# foc_board.net
KiCad netlist of a schematic drawn in EasyEDA Pro
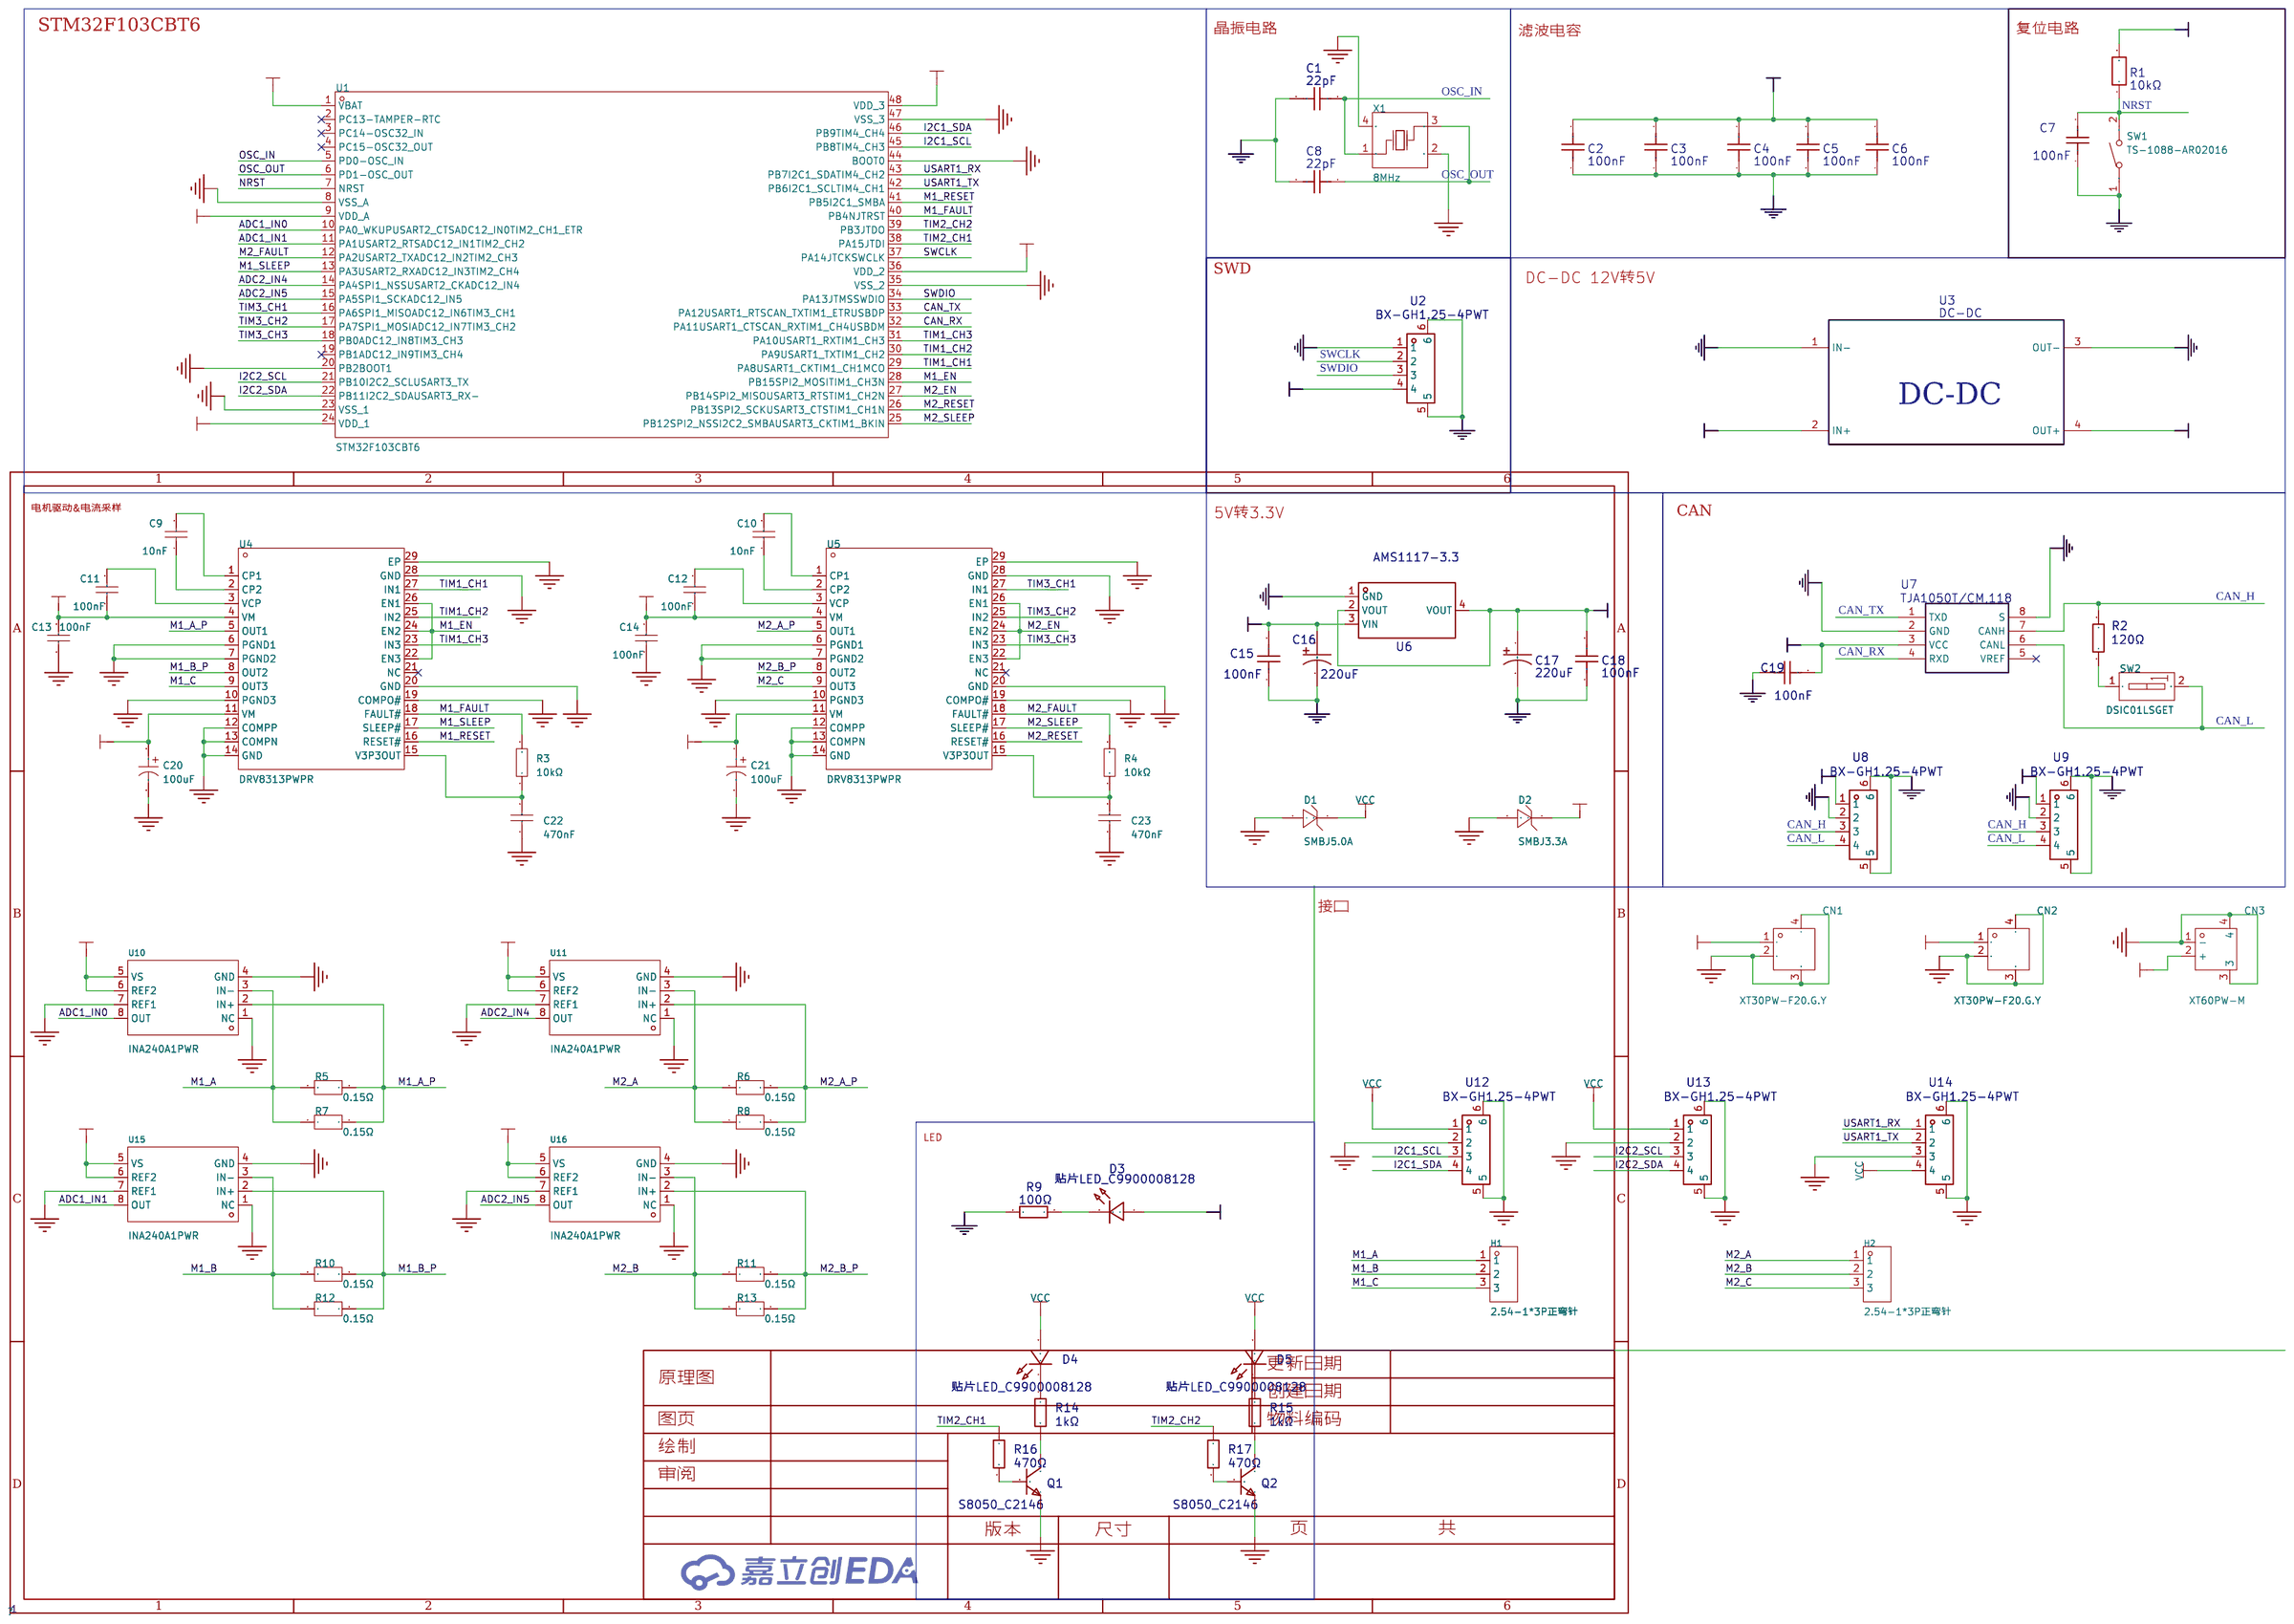
[diagram p0: schematic sheet]

(export (version "E")
  (design (tool "Eeschema 10.0.6"))
  (components
    (comp (ref "C1")
      (value "22pF")
      (footprint "easyedapro:C0603")
      (fields
        (field (name "Manufacturer Part") "0603J0250104KXR")
        (field (name "Manufacturer") "Knowles(楼氏)")
      )
      (libsource (lib "easyedapro") (part "22pF"))
    )
    (comp (ref "C2")
      (value "100nF")
      (footprint "easyedapro:C0603")
      (fields
        (field (name "Manufacturer Part") "0603J0250104KXR")
        (field (name "Manufacturer") "Knowles(楼氏)")
      )
      (libsource (lib "easyedapro") (part "100nF"))
    )
    (comp (ref "C3")
      (value "100nF")
      (footprint "easyedapro:C0603")
      (fields
        (field (name "Manufacturer Part") "0603J0250104KXR")
        (field (name "Manufacturer") "Knowles(楼氏)")
      )
      (libsource (lib "easyedapro") (part "100nF"))
    )
    (comp (ref "C4")
      (value "100nF")
      (footprint "easyedapro:C0603")
      (fields
        (field (name "Manufacturer Part") "0603J0250104KXR")
        (field (name "Manufacturer") "Knowles(楼氏)")
      )
      (libsource (lib "easyedapro") (part "100nF"))
    )
    (comp (ref "C5")
      (value "100nF")
      (footprint "easyedapro:C0603")
      (fields
        (field (name "Manufacturer Part") "0603J0250104KXR")
        (field (name "Manufacturer") "Knowles(楼氏)")
      )
      (libsource (lib "easyedapro") (part "100nF"))
    )
    (comp (ref "C6")
      (value "100nF")
      (footprint "easyedapro:C0603")
      (fields
        (field (name "Manufacturer Part") "0603J0250104KXR")
        (field (name "Manufacturer") "Knowles(楼氏)")
      )
      (libsource (lib "easyedapro") (part "100nF"))
    )
    (comp (ref "C7")
      (value "100nF")
      (footprint "easyedapro:C0603")
      (fields
        (field (name "Manufacturer Part") "0603J0250104KXR")
        (field (name "Manufacturer") "Knowles(楼氏)")
      )
      (libsource (lib "easyedapro") (part "100nF"))
    )
    (comp (ref "C8")
      (value "22pF")
      (footprint "easyedapro:C0603")
      (fields
        (field (name "Manufacturer Part") "0603J0250104KXR")
        (field (name "Manufacturer") "Knowles(楼氏)")
      )
      (libsource (lib "easyedapro") (part "22pF"))
    )
    (comp (ref "C9")
      (value "10nF")
      (footprint "easyedapro:C0603")
      (description "容值:10nF;精度:±10%;额定电压:50V;材质(温度系数):X7R;")
      (fields
        (field (name "Manufacturer Part") "CC0603KRX7R9BB103")
        (field (name "Manufacturer") "YAGEO(国巨)")
      )
      (libsource (lib "easyedapro") (part "CC0603KRX7R9BB103"))
    )
    (comp (ref "C10")
      (value "10nF")
      (footprint "easyedapro:C0603")
      (description "容值:10nF;精度:±10%;额定电压:50V;材质(温度系数):X7R;")
      (fields
        (field (name "Manufacturer Part") "CC0603KRX7R9BB103")
        (field (name "Manufacturer") "YAGEO(国巨)")
      )
      (libsource (lib "easyedapro") (part "CC0603KRX7R9BB103"))
    )
    (comp (ref "C11")
      (value "100nF")
      (footprint "easyedapro:C0603")
      (description "容值:10nF;精度:±10%;额定电压:50V;材质(温度系数):X7R;")
      (fields
        (field (name "Manufacturer Part") "CC0603KRX7R9BB103")
        (field (name "Manufacturer") "YAGEO(国巨)")
      )
      (libsource (lib "easyedapro") (part "CC0603KRX7R9BB103"))
    )
    (comp (ref "C12")
      (value "100nF")
      (footprint "easyedapro:C0603")
      (description "容值:10nF;精度:±10%;额定电压:50V;材质(温度系数):X7R;")
      (fields
        (field (name "Manufacturer Part") "CC0603KRX7R9BB103")
        (field (name "Manufacturer") "YAGEO(国巨)")
      )
      (libsource (lib "easyedapro") (part "CC0603KRX7R9BB103"))
    )
    (comp (ref "C13")
      (value "100nF")
      (footprint "easyedapro:C0603")
      (description "容值:10nF;精度:±10%;额定电压:50V;材质(温度系数):X7R;")
      (fields
        (field (name "Manufacturer Part") "CC0603KRX7R9BB103")
        (field (name "Manufacturer") "YAGEO(国巨)")
      )
      (libsource (lib "easyedapro") (part "CC0603KRX7R9BB103"))
    )
    (comp (ref "C14")
      (value "100nF")
      (footprint "easyedapro:C0603")
      (description "容值:10nF;精度:±10%;额定电压:50V;材质(温度系数):X7R;")
      (fields
        (field (name "Manufacturer Part") "CC0603KRX7R9BB103")
        (field (name "Manufacturer") "YAGEO(国巨)")
      )
      (libsource (lib "easyedapro") (part "CC0603KRX7R9BB103"))
    )
    (comp (ref "C15")
      (value "100nF")
      (footprint "easyedapro:C0603")
      (fields
        (field (name "Manufacturer Part") "0603J0250104KXR")
        (field (name "Manufacturer") "Knowles(楼氏)")
      )
      (libsource (lib "easyedapro") (part "100nF"))
    )
    (comp (ref "C16")
      (value "220uF")
      (footprint "easyedapro:CAP-SMD_BD6.3-L6.6-W6.6-FD")
      (fields
        (field (name "Manufacturer Part") "MVK 16V220M 6.3*8 6.3TP")
        (field (name "Manufacturer") "SAMYOUNG(韩国三莹)")
      )
      (libsource (lib "easyedapro") (part "220uF"))
    )
    (comp (ref "C17")
      (value "220uF")
      (footprint "easyedapro:CAP-SMD_BD6.3-L6.6-W6.6-FD")
      (fields
        (field (name "Manufacturer Part") "MVK 16V220M 6.3*8 6.3TP")
        (field (name "Manufacturer") "SAMYOUNG(韩国三莹)")
      )
      (libsource (lib "easyedapro") (part "220uF"))
    )
    (comp (ref "C18")
      (value "100nF")
      (footprint "easyedapro:C0603")
      (fields
        (field (name "Manufacturer Part") "0603J0250104KXR")
        (field (name "Manufacturer") "Knowles(楼氏)")
      )
      (libsource (lib "easyedapro") (part "100nF"))
    )
    (comp (ref "C19")
      (value "100nF")
      (footprint "easyedapro:C0603")
      (fields
        (field (name "Manufacturer Part") "0603J0250104KXR")
        (field (name "Manufacturer") "Knowles(楼氏)")
      )
      (libsource (lib "easyedapro") (part "100nF"))
    )
    (comp (ref "C20")
      (value "100uF")
      (footprint "easyedapro:CAP-SMD_BD6.3-L6.6-W6.6-LS7.4-FD")
      (description "容值:100uF;精度:±20%;额定电压:35V;纹波电流:87mA@120kHz;等效串联电阻:-;")
      (fields
        (field (name "Manufacturer Part") "RVT100UF35V67RV0034")
        (field (name "Manufacturer") "KNSCHA(科尼盛)")
      )
      (libsource (lib "easyedapro") (part "RVT100UF35V67RV0034"))
    )
    (comp (ref "C21")
      (value "100uF")
      (footprint "easyedapro:CAP-SMD_BD6.3-L6.6-W6.6-LS7.4-FD")
      (description "容值:100uF;精度:±20%;额定电压:35V;纹波电流:87mA@120kHz;等效串联电阻:-;")
      (fields
        (field (name "Manufacturer Part") "RVT100UF35V67RV0034")
        (field (name "Manufacturer") "KNSCHA(科尼盛)")
      )
      (libsource (lib "easyedapro") (part "RVT100UF35V67RV0034"))
    )
    (comp (ref "C22")
      (value "470nF")
      (footprint "easyedapro:C0603")
      (description "容值:470nF;精度:±10%;额定电压:25V;材质(温度系数):X7R;")
      (fields
        (field (name "Manufacturer Part") "CL10B474KA8NNNC")
        (field (name "Manufacturer") "SAMSUNG(三星)")
      )
      (libsource (lib "easyedapro") (part "CL10B474KA8NNNC"))
    )
    (comp (ref "C23")
      (value "470nF")
      (footprint "easyedapro:C0603")
      (description "容值:470nF;精度:±10%;额定电压:25V;材质(温度系数):X7R;")
      (fields
        (field (name "Manufacturer Part") "CL10B474KA8NNNC")
        (field (name "Manufacturer") "SAMSUNG(三星)")
      )
      (libsource (lib "easyedapro") (part "CL10B474KA8NNNC"))
    )
    (comp (ref "CN1")
      (value "XT30PW-F20.G.Y")
      (footprint "easyedapro:CONN-TH_XT30PW-F-1")
      (description "类别:-;类型1:-;")
      (fields (field (name "Manufacturer") "AMASS(艾迈斯)"))
      (libsource (lib "easyedapro") (part "XT30PW-F"))
    )
    (comp (ref "CN2")
      (value "XT30PW-F20.G.Y")
      (footprint "easyedapro:CONN-TH_XT30PW-F-1")
      (description "类别:-;类型1:-;")
      (fields (field (name "Manufacturer") "AMASS(艾迈斯)"))
      (libsource (lib "easyedapro") (part "XT30PW-F"))
    )
    (comp (ref "CN3")
      (value "XT60PW-M")
      (footprint "easyedapro:CONN-TH_XT60PW-M")
      (description "类别:-;类型1:-;")
      (fields (field (name "Manufacturer") "AMASS(艾迈斯)"))
      (libsource (lib "easyedapro") (part "XT60PW-M"))
    )
    (comp (ref "D1")
      (value "SMBJ5.0A")
      (footprint "easyedapro:SMB_L4.6-W3.6-LS5.3-RD")
      (description "反向截止电压(Vrwm):5V;最大钳位电压:9.2V;峰值脉冲电流(Ipp)@10/1000us:65.2A;击穿电压:6.4V;")
      (fields (field (name "Manufacturer") "MDD"))
      (libsource (lib "easyedapro") (part "SMBJ5.0A-C113974"))
    )
    (comp (ref "D2")
      (value "SMBJ3.3A")
      (footprint "easyedapro:SMB_L4.6-W3.6-LS5.3-RD")
      (description "反向截止电压(Vrwm):3.3V;最大钳位电压:7.3V;峰值脉冲功率(Ppp)@10/1000us:600W;击穿电压:4.1V;")
      (fields (field (name "Manufacturer") "JKSEMI(金开盛)"))
      (libsource (lib "easyedapro") (part "SMBJ3.3A_C362089"))
    )
    (comp (ref "D3")
      (value "贴片LED_C9900008128")
      (footprint "easyedapro:LED0603-RD")
      (fields (field (name "Manufacturer Part") "贴片LED"))
      (libsource (lib "easyedapro") (part "贴片LED_C9900008128"))
    )
    (comp (ref "D4")
      (value "贴片LED_C9900008128")
      (footprint "easyedapro:LED0603-RD")
      (fields (field (name "Manufacturer Part") "贴片LED"))
      (libsource (lib "easyedapro") (part "贴片LED_C9900008128"))
    )
    (comp (ref "D5")
      (value "贴片LED_C9900008128")
      (footprint "easyedapro:LED0603-RD")
      (fields (field (name "Manufacturer Part") "贴片LED"))
      (libsource (lib "easyedapro") (part "贴片LED_C9900008128"))
    )
    (comp (ref "H1")
      (value "2.54-1*3P正弯针")
      (footprint "easyedapro:HDR-TH_3P-P2.54-H-M-BW7.2-P")
      (fields (field (name "Manufacturer") "BOOMELE(博穆精密)"))
      (libsource (lib "easyedapro") (part "C92159"))
    )
    (comp (ref "H2")
      (value "2.54-1*3P正弯针")
      (footprint "easyedapro:HDR-TH_3P-P2.54-H-M-BW7.2-P")
      (fields (field (name "Manufacturer") "BOOMELE(博穆精密)"))
      (libsource (lib "easyedapro") (part "C92159"))
    )
    (comp (ref "Q1")
      (value "S8050_C2146")
      (footprint "easyedapro:SOT-23-3_L3.0-W1.7-P0.95-LS2.9-BR")
      (fields (field (name "Manufacturer Part") "S8050 J3Y") (field (name "Manufacturer") "CJ(江苏长电/长晶)"))
      (libsource (lib "easyedapro") (part "S8050_C2146"))
    )
    (comp (ref "Q2")
      (value "S8050_C2146")
      (footprint "easyedapro:SOT-23-3_L3.0-W1.7-P0.95-LS2.9-BR")
      (fields (field (name "Manufacturer Part") "S8050 J3Y") (field (name "Manufacturer") "CJ(江苏长电/长晶)"))
      (libsource (lib "easyedapro") (part "S8050_C2146"))
    )
    (comp (ref "R1")
      (value "10kΩ")
      (footprint "easyedapro:R0603")
      (fields
        (field (name "Manufacturer Part") "MCT0603MG1002BP500")
        (field (name "Manufacturer") "VISHAY(威世)")
      )
      (libsource (lib "easyedapro") (part "10kΩ"))
    )
    (comp (ref "R2")
      (value "120Ω")
      (footprint "easyedapro:R0805")
      (fields (field (name "Manufacturer Part") "RC0805FR-07120RL") (field (name "Manufacturer") "YAGEO(国巨)"))
      (libsource (lib "easyedapro") (part "120Ω"))
    )
    (comp (ref "R3")
      (value "10kΩ")
      (footprint "easyedapro:R0603")
      (description "电阻类型:厚膜电阻;阻值:10kΩ;精度:±1%;功率:100mW;最大工作电压:75V;温度系数:±100ppm/°C;")
      (fields
        (field (name "Manufacturer Part") "0603WAF1002T5E")
        (field (name "Manufacturer") "UNI-ROYAL(厚声)")
      )
      (libsource (lib "easyedapro") (part "0603WAF1002T5E"))
    )
    (comp (ref "R4")
      (value "10kΩ")
      (footprint "easyedapro:R0603")
      (description "电阻类型:厚膜电阻;阻值:10kΩ;精度:±1%;功率:100mW;最大工作电压:75V;温度系数:±100ppm/°C;")
      (fields
        (field (name "Manufacturer Part") "0603WAF1002T5E")
        (field (name "Manufacturer") "UNI-ROYAL(厚声)")
      )
      (libsource (lib "easyedapro") (part "0603WAF1002T5E"))
    )
    (comp (ref "R5")
      (value "0.15Ω")
      (footprint "easyedapro:R1812")
      (description "电阻类型:厚膜电阻;阻值:100Ω;精度:±5%;功率:750mW;最大工作电压:200V;温度系数:±100ppm/°C;")
      (fields (field (name "Manufacturer Part") "FRC1812J101 TS") (field (name "Manufacturer") "FOJAN(富捷)"))
      (libsource (lib "easyedapro") (part "FRC1812J101 TS"))
    )
    (comp (ref "R6")
      (value "0.15Ω")
      (footprint "easyedapro:R1812")
      (description "电阻类型:厚膜电阻;阻值:100Ω;精度:±5%;功率:750mW;最大工作电压:200V;温度系数:±100ppm/°C;")
      (fields (field (name "Manufacturer Part") "FRC1812J101 TS") (field (name "Manufacturer") "FOJAN(富捷)"))
      (libsource (lib "easyedapro") (part "FRC1812J101 TS"))
    )
    (comp (ref "R7")
      (value "0.15Ω")
      (footprint "easyedapro:R1812")
      (description "电阻类型:厚膜电阻;阻值:100Ω;精度:±5%;功率:750mW;最大工作电压:200V;温度系数:±100ppm/°C;")
      (fields (field (name "Manufacturer Part") "FRC1812J101 TS") (field (name "Manufacturer") "FOJAN(富捷)"))
      (libsource (lib "easyedapro") (part "FRC1812J101 TS"))
    )
    (comp (ref "R8")
      (value "0.15Ω")
      (footprint "easyedapro:R1812")
      (description "电阻类型:厚膜电阻;阻值:100Ω;精度:±5%;功率:750mW;最大工作电压:200V;温度系数:±100ppm/°C;")
      (fields (field (name "Manufacturer Part") "FRC1812J101 TS") (field (name "Manufacturer") "FOJAN(富捷)"))
      (libsource (lib "easyedapro") (part "FRC1812J101 TS"))
    )
    (comp (ref "R9")
      (value "100Ω")
      (footprint "easyedapro:R0805")
      (fields (field (name "Manufacturer Part") "RC0805FR-07120RL") (field (name "Manufacturer") "YAGEO(国巨)"))
      (libsource (lib "easyedapro") (part "1kΩ"))
    )
    (comp (ref "R10")
      (value "0.15Ω")
      (footprint "easyedapro:R1812")
      (description "电阻类型:厚膜电阻;阻值:100Ω;精度:±5%;功率:750mW;最大工作电压:200V;温度系数:±100ppm/°C;")
      (fields (field (name "Manufacturer Part") "FRC1812J101 TS") (field (name "Manufacturer") "FOJAN(富捷)"))
      (libsource (lib "easyedapro") (part "FRC1812J101 TS"))
    )
    (comp (ref "R11")
      (value "0.15Ω")
      (footprint "easyedapro:R1812")
      (description "电阻类型:厚膜电阻;阻值:100Ω;精度:±5%;功率:750mW;最大工作电压:200V;温度系数:±100ppm/°C;")
      (fields (field (name "Manufacturer Part") "FRC1812J101 TS") (field (name "Manufacturer") "FOJAN(富捷)"))
      (libsource (lib "easyedapro") (part "FRC1812J101 TS"))
    )
    (comp (ref "R12")
      (value "0.15Ω")
      (footprint "easyedapro:R1812")
      (description "电阻类型:厚膜电阻;阻值:100Ω;精度:±5%;功率:750mW;最大工作电压:200V;温度系数:±100ppm/°C;")
      (fields (field (name "Manufacturer Part") "FRC1812J101 TS") (field (name "Manufacturer") "FOJAN(富捷)"))
      (libsource (lib "easyedapro") (part "FRC1812J101 TS"))
    )
    (comp (ref "R13")
      (value "0.15Ω")
      (footprint "easyedapro:R1812")
      (description "电阻类型:厚膜电阻;阻值:100Ω;精度:±5%;功率:750mW;最大工作电压:200V;温度系数:±100ppm/°C;")
      (fields (field (name "Manufacturer Part") "FRC1812J101 TS") (field (name "Manufacturer") "FOJAN(富捷)"))
      (libsource (lib "easyedapro") (part "FRC1812J101 TS"))
    )
    (comp (ref "R14")
      (value "1kΩ")
      (footprint "easyedapro:R0805")
      (fields (field (name "Manufacturer Part") "RC0805FR-07120RL") (field (name "Manufacturer") "YAGEO(国巨)"))
      (libsource (lib "easyedapro") (part "1kΩ"))
    )
    (comp (ref "R15")
      (value "1kΩ")
      (footprint "easyedapro:R0805")
      (fields (field (name "Manufacturer Part") "RC0805FR-07120RL") (field (name "Manufacturer") "YAGEO(国巨)"))
      (libsource (lib "easyedapro") (part "1kΩ"))
    )
    (comp (ref "R16")
      (value "470Ω")
      (footprint "easyedapro:R0805")
      (fields (field (name "Manufacturer Part") "RC0805FR-07120RL") (field (name "Manufacturer") "YAGEO(国巨)"))
      (libsource (lib "easyedapro") (part "1kΩ"))
    )
    (comp (ref "R17")
      (value "470Ω")
      (footprint "easyedapro:R0805")
      (fields (field (name "Manufacturer Part") "RC0805FR-07120RL") (field (name "Manufacturer") "YAGEO(国巨)"))
      (libsource (lib "easyedapro") (part "1kΩ"))
    )
    (comp (ref "SW1")
      (value "TS-1088-AR02016")
      (footprint "easyedapro:SW-SMD_L3.9-W3.0-P4.45")
      (fields (field (name "Manufacturer") "XUNPU(讯普)"))
      (libsource (lib "easyedapro") (part "TS-1088-AR02016"))
    )
    (comp (ref "SW2")
      (value "DSIC01LSGET")
      (footprint "easyedapro:SW-SMD_DSIC01LSGET")
      (description "类型:平拨,凸起式;电路结构:单刀单掷;开关位数:1位;使用寿命:-;颜色:黑色;")
      (fields (field (name "Manufacturer") "YE"))
      (libsource (lib "easyedapro") (part "DSIC01LSGET"))
    )
    (comp (ref "U1")
      (value "STM32F103CBT6")
      (footprint "easyedapro:LQFP-48_L7.0-W7.0-P0.50-LS9.0-BL")
      (description "CPU内核:ARM-M3;程序存储容量:128KB;RAM总容量:20KB;GPIO端口数量:37;工作电压范围:2V~3.6V;CPU最大主频:72MHz;程序存储器类型:FLASH;")
      (fields (field (name "Manufacturer") "ST(意法半导体)"))
      (libsource (lib "easyedapro") (part "STM32F103CBT6"))
    )
    (comp (ref "U2")
      (value "BX-GH1.25-4PWT")
      (footprint "easyedapro:CONN-SMD_4P-P1.25_BX-GH1.25-4PWT")
      (fields (field (name "Manufacturer") "Bossie(博锡)"))
      (libsource (lib "easyedapro") (part "BX-GH1.25-4PWT"))
    )
    (comp (ref "U3")
      (value "DC-DC")
      (footprint "easyedapro:DC-DC")
      (libsource (lib "easyedapro") (part "DC-DC"))
    )
    (comp (ref "U4")
      (value "DRV8313PWPR")
      (footprint "easyedapro:HTSSOP-28_L9.8-W4.5-P0.65-LS6.6-BL-EP")
      (description "DRV8313 具有集成 FET、65V 最大电压、3A 峰值电流的三相电机驱动器")
      (fields (field (name "Manufacturer") "TI(德州仪器)"))
      (libsource (lib "easyedapro") (part "DRV8313PWPR"))
    )
    (comp (ref "U5")
      (value "DRV8313PWPR")
      (footprint "easyedapro:HTSSOP-28_L9.8-W4.5-P0.65-LS6.6-BL-EP")
      (description "DRV8313 具有集成 FET、65V 最大电压、3A 峰值电流的三相电机驱动器")
      (fields (field (name "Manufacturer") "TI(德州仪器)"))
      (libsource (lib "easyedapro") (part "DRV8313PWPR"))
    )
    (comp (ref "U6")
      (value "AMS1117-3.3")
      (footprint "easyedapro:SOT-223-3_L6.5-W3.4-P2.30-LS7.0-BR")
      (fields (field (name "Manufacturer") "AMS"))
      (libsource (lib "easyedapro") (part "AMS1117-3.3"))
    )
    (comp (ref "U7")
      (value "TJA1050T/CM,118")
      (footprint "easyedapro:SOIC-8_L5.0-W4.0-P1.27-LS6.0-BL")
      (fields (field (name "Manufacturer") "NXP(恩智浦)"))
      (libsource (lib "easyedapro") (part "TJA1050T/CM,118"))
    )
    (comp (ref "U8")
      (value "BX-GH1.25-4PWT")
      (footprint "easyedapro:CONN-SMD_4P-P1.25_BX-GH1.25-4PWT")
      (fields (field (name "Manufacturer") "Bossie(博锡)"))
      (libsource (lib "easyedapro") (part "BX-GH1.25-4PWT"))
    )
    (comp (ref "U9")
      (value "BX-GH1.25-4PWT")
      (footprint "easyedapro:CONN-SMD_4P-P1.25_BX-GH1.25-4PWT")
      (fields (field (name "Manufacturer") "Bossie(博锡)"))
      (libsource (lib "easyedapro") (part "BX-GH1.25-4PWT"))
    )
    (comp (ref "U10")
      (value "INA240A1PWR")
      (footprint "easyedapro:TSSOP-8_L4.4-W3.0-P0.65-LS6.4-BL")
      (description "放大器数:单路;")
      (fields (field (name "Manufacturer") "TI(德州仪器)"))
      (libsource (lib "easyedapro") (part "INA240A1PWR"))
    )
    (comp (ref "U11")
      (value "INA240A1PWR")
      (footprint "easyedapro:TSSOP-8_L4.4-W3.0-P0.65-LS6.4-BL")
      (description "放大器数:单路;")
      (fields (field (name "Manufacturer") "TI(德州仪器)"))
      (libsource (lib "easyedapro") (part "INA240A1PWR"))
    )
    (comp (ref "U12")
      (value "BX-GH1.25-4PWT")
      (footprint "easyedapro:CONN-SMD_4P-P1.25_BX-GH1.25-4PWT")
      (fields (field (name "Manufacturer") "Bossie(博锡)"))
      (libsource (lib "easyedapro") (part "BX-GH1.25-4PWT"))
    )
    (comp (ref "U13")
      (value "BX-GH1.25-4PWT")
      (footprint "easyedapro:CONN-SMD_4P-P1.25_BX-GH1.25-4PWT")
      (fields (field (name "Manufacturer") "Bossie(博锡)"))
      (libsource (lib "easyedapro") (part "BX-GH1.25-4PWT"))
    )
    (comp (ref "U14")
      (value "BX-GH1.25-4PWT")
      (footprint "easyedapro:CONN-SMD_4P-P1.25_BX-GH1.25-4PWT")
      (fields (field (name "Manufacturer") "Bossie(博锡)"))
      (libsource (lib "easyedapro") (part "BX-GH1.25-4PWT"))
    )
    (comp (ref "U15")
      (value "INA240A1PWR")
      (footprint "easyedapro:TSSOP-8_L4.4-W3.0-P0.65-LS6.4-BL")
      (description "放大器数:单路;")
      (fields (field (name "Manufacturer") "TI(德州仪器)"))
      (libsource (lib "easyedapro") (part "INA240A1PWR"))
    )
    (comp (ref "U16")
      (value "INA240A1PWR")
      (footprint "easyedapro:TSSOP-8_L4.4-W3.0-P0.65-LS6.4-BL")
      (description "放大器数:单路;")
      (fields (field (name "Manufacturer") "TI(德州仪器)"))
      (libsource (lib "easyedapro") (part "INA240A1PWR"))
    )
    (comp (ref "X1")
      (value "8MHz")
      (footprint "easyedapro:OSC-SMD_4P-L5.0-W3.2-BL")
      (description "晶振类型:贴片晶振;频率:8MHz;常温频差:±10ppm;外接负载电容:20pF;频率稳定度(全温):±20ppm;")
      (fields (field (name "Manufacturer Part") "X50328MSB4SI") (field (name "Manufacturer") "YXC(扬兴晶振)"))
      (libsource (lib "easyedapro") (part "X50328MSB4SI"))
    )
  )
  (nets
    (net (code "1") (name "/ADC1_IN0") (class "Default")
      (node (ref "U1") (pin "10") (pinfunction "PA0_WKUPUSART2_CTSADC12_IN0TIM2_CH1_ETR_10") (pintype "unspecified"))
      (node (ref "U10") (pin "8") (pinfunction "OUT_8") (pintype "input"))
    )
    (net (code "2") (name "/ADC1_IN1") (class "Default")
      (node (ref "U1") (pin "11") (pinfunction "PA1USART2_RTSADC12_IN1TIM2_CH2_11") (pintype "unspecified"))
      (node (ref "U15") (pin "8") (pinfunction "OUT_8") (pintype "input"))
    )
    (net (code "3") (name "/ADC2_IN4") (class "Default")
      (node (ref "U1") (pin "14") (pinfunction "PA4SPI1_NSSUSART2_CKADC12_IN4_14") (pintype "unspecified"))
      (node (ref "U11") (pin "8") (pinfunction "OUT_8") (pintype "input"))
    )
    (net (code "4") (name "/ADC2_IN5") (class "Default")
      (node (ref "U1") (pin "15") (pinfunction "PA5SPI1_SCKADC12_IN5_15") (pintype "unspecified"))
      (node (ref "U16") (pin "8") (pinfunction "OUT_8") (pintype "input"))
    )
    (net (code "5") (name "/CAN_H") (class "Default")
      (node (ref "R2") (pin "2") (pinfunction "2_2") (pintype "input"))
      (node (ref "U7") (pin "7") (pinfunction "CANH_7") (pintype "unspecified"))
      (node (ref "U8") (pin "3") (pinfunction "3_3") (pintype "unspecified"))
      (node (ref "U9") (pin "3") (pinfunction "3_3") (pintype "unspecified"))
    )
    (net (code "6") (name "/CAN_L") (class "Default")
      (node (ref "SW2") (pin "2") (pinfunction "A2_2") (pintype "input"))
      (node (ref "U7") (pin "6") (pinfunction "CANL_6") (pintype "unspecified"))
      (node (ref "U8") (pin "4") (pinfunction "4_4") (pintype "unspecified"))
      (node (ref "U9") (pin "4") (pinfunction "4_4") (pintype "unspecified"))
    )
    (net (code "7") (name "/CAN_RX") (class "Default")
      (node (ref "U1") (pin "32") (pinfunction "PA11USART1_CTSCAN_RXTIM1_CH4USBDM_32") (pintype "unspecified"))
      (node (ref "U7") (pin "4") (pinfunction "RXD_4") (pintype "unspecified"))
    )
    (net (code "8") (name "/CAN_TX") (class "Default")
      (node (ref "U1") (pin "33") (pinfunction "PA12USART1_RTSCAN_TXTIM1_ETRUSBDP_33") (pintype "unspecified"))
      (node (ref "U7") (pin "1") (pinfunction "TXD_1") (pintype "unspecified"))
    )
    (net (code "9") (name "/I2C1_SCL") (class "Default")
      (node (ref "U1") (pin "45") (pinfunction "PB8TIM4_CH3_45") (pintype "unspecified"))
      (node (ref "U12") (pin "3") (pinfunction "3_3") (pintype "unspecified"))
    )
    (net (code "10") (name "/I2C1_SDA") (class "Default")
      (node (ref "U1") (pin "46") (pinfunction "PB9TIM4_CH4_46") (pintype "unspecified"))
      (node (ref "U12") (pin "4") (pinfunction "4_4") (pintype "unspecified"))
    )
    (net (code "11") (name "/I2C2_SCL") (class "Default")
      (node (ref "U1") (pin "21") (pinfunction "PB10I2C2_SCLUSART3_TX_21") (pintype "unspecified"))
      (node (ref "U13") (pin "3") (pinfunction "3_3") (pintype "unspecified"))
    )
    (net (code "12") (name "/I2C2_SDA") (class "Default")
      (node (ref "U1") (pin "22") (pinfunction "PB11I2C2_SDAUSART3_RX-_22") (pintype "unspecified"))
      (node (ref "U13") (pin "4") (pinfunction "4_4") (pintype "unspecified"))
    )
    (net (code "13") (name "/M1_A") (class "Default")
      (node (ref "H1") (pin "1") (pinfunction "1_1") (pintype "input"))
      (node (ref "R5") (pin "1") (pinfunction "1_1") (pintype "unspecified"))
      (node (ref "R7") (pin "1") (pinfunction "1_1") (pintype "unspecified"))
      (node (ref "U10") (pin "3") (pinfunction "IN-_3") (pintype "input"))
    )
    (net (code "14") (name "/M1_A_P") (class "Default")
      (node (ref "R5") (pin "2") (pinfunction "2_2") (pintype "unspecified"))
      (node (ref "R7") (pin "2") (pinfunction "2_2") (pintype "unspecified"))
      (node (ref "U10") (pin "2") (pinfunction "IN+_2") (pintype "input"))
      (node (ref "U4") (pin "5") (pinfunction "OUT1_5") (pintype "unspecified"))
    )
    (net (code "15") (name "/M1_B") (class "Default")
      (node (ref "H1") (pin "2") (pinfunction "2_2") (pintype "input"))
      (node (ref "R10") (pin "1") (pinfunction "1_1") (pintype "unspecified"))
      (node (ref "R12") (pin "1") (pinfunction "1_1") (pintype "unspecified"))
      (node (ref "U15") (pin "3") (pinfunction "IN-_3") (pintype "input"))
    )
    (net (code "16") (name "/M1_B_P") (class "Default")
      (node (ref "R10") (pin "2") (pinfunction "2_2") (pintype "unspecified"))
      (node (ref "R12") (pin "2") (pinfunction "2_2") (pintype "unspecified"))
      (node (ref "U15") (pin "2") (pinfunction "IN+_2") (pintype "input"))
      (node (ref "U4") (pin "8") (pinfunction "OUT2_8") (pintype "unspecified"))
    )
    (net (code "17") (name "/M1_C") (class "Default")
      (node (ref "H1") (pin "3") (pinfunction "3_3") (pintype "input"))
      (node (ref "U4") (pin "9") (pinfunction "OUT3_9") (pintype "unspecified"))
    )
    (net (code "18") (name "/M1_EN") (class "Default")
      (node (ref "U1") (pin "28") (pinfunction "PB15SPI2_MOSITIM1_CH3N_28") (pintype "unspecified"))
      (node (ref "U4") (pin "22") (pinfunction "EN3_22") (pintype "unspecified"))
      (node (ref "U4") (pin "24") (pinfunction "EN2_24") (pintype "unspecified"))
      (node (ref "U4") (pin "26") (pinfunction "EN1_26") (pintype "unspecified"))
    )
    (net (code "19") (name "/M1_FAULT") (class "Default")
      (node (ref "R3") (pin "2") (pinfunction "2_2") (pintype "input"))
      (node (ref "U1") (pin "40") (pinfunction "PB4NJTRST_40") (pintype "unspecified"))
      (node (ref "U4") (pin "18") (pinfunction "FAULT#_18") (pintype "unspecified"))
    )
    (net (code "20") (name "/M1_RESET") (class "Default")
      (node (ref "U1") (pin "41") (pinfunction "PB5I2C1_SMBA_41") (pintype "unspecified"))
      (node (ref "U4") (pin "16") (pinfunction "RESET#_16") (pintype "unspecified"))
    )
    (net (code "21") (name "/M1_SLEEP") (class "Default")
      (node (ref "U1") (pin "13") (pinfunction "PA3USART2_RXADC12_IN3TIM2_CH4_13") (pintype "unspecified"))
      (node (ref "U4") (pin "17") (pinfunction "SLEEP#_17") (pintype "unspecified"))
    )
    (net (code "22") (name "/M2_A") (class "Default")
      (node (ref "H2") (pin "1") (pinfunction "1_1") (pintype "input"))
      (node (ref "R6") (pin "1") (pinfunction "1_1") (pintype "unspecified"))
      (node (ref "R8") (pin "1") (pinfunction "1_1") (pintype "unspecified"))
      (node (ref "U11") (pin "3") (pinfunction "IN-_3") (pintype "input"))
    )
    (net (code "23") (name "/M2_A_P") (class "Default")
      (node (ref "R6") (pin "2") (pinfunction "2_2") (pintype "unspecified"))
      (node (ref "R8") (pin "2") (pinfunction "2_2") (pintype "unspecified"))
      (node (ref "U11") (pin "2") (pinfunction "IN+_2") (pintype "input"))
      (node (ref "U5") (pin "5") (pinfunction "OUT1_5") (pintype "unspecified"))
    )
    (net (code "24") (name "/M2_B") (class "Default")
      (node (ref "H2") (pin "2") (pinfunction "2_2") (pintype "input"))
      (node (ref "R11") (pin "1") (pinfunction "1_1") (pintype "unspecified"))
      (node (ref "R13") (pin "1") (pinfunction "1_1") (pintype "unspecified"))
      (node (ref "U16") (pin "3") (pinfunction "IN-_3") (pintype "input"))
    )
    (net (code "25") (name "/M2_B_P") (class "Default")
      (node (ref "R11") (pin "2") (pinfunction "2_2") (pintype "unspecified"))
      (node (ref "R13") (pin "2") (pinfunction "2_2") (pintype "unspecified"))
      (node (ref "U16") (pin "2") (pinfunction "IN+_2") (pintype "input"))
      (node (ref "U5") (pin "8") (pinfunction "OUT2_8") (pintype "unspecified"))
    )
    (net (code "26") (name "/M2_C") (class "Default")
      (node (ref "H2") (pin "3") (pinfunction "3_3") (pintype "input"))
      (node (ref "U5") (pin "9") (pinfunction "OUT3_9") (pintype "unspecified"))
    )
    (net (code "27") (name "/M2_EN") (class "Default")
      (node (ref "U1") (pin "27") (pinfunction "PB14SPI2_MISOUSART3_RTSTIM1_CH2N_27") (pintype "unspecified"))
      (node (ref "U5") (pin "22") (pinfunction "EN3_22") (pintype "unspecified"))
      (node (ref "U5") (pin "24") (pinfunction "EN2_24") (pintype "unspecified"))
      (node (ref "U5") (pin "26") (pinfunction "EN1_26") (pintype "unspecified"))
    )
    (net (code "28") (name "/M2_FAULT") (class "Default")
      (node (ref "R4") (pin "2") (pinfunction "2_2") (pintype "input"))
      (node (ref "U1") (pin "12") (pinfunction "PA2USART2_TXADC12_IN2TIM2_CH3_12") (pintype "unspecified"))
      (node (ref "U5") (pin "18") (pinfunction "FAULT#_18") (pintype "unspecified"))
    )
    (net (code "29") (name "/M2_RESET") (class "Default")
      (node (ref "U1") (pin "26") (pinfunction "PB13SPI2_SCKUSART3_CTSTIM1_CH1N_26") (pintype "unspecified"))
      (node (ref "U5") (pin "16") (pinfunction "RESET#_16") (pintype "unspecified"))
    )
    (net (code "30") (name "/M2_SLEEP") (class "Default")
      (node (ref "U1") (pin "25") (pinfunction "PB12SPI2_NSSI2C2_SMBAUSART3_CKTIM1_BKIN_25") (pintype "unspecified"))
      (node (ref "U5") (pin "17") (pinfunction "SLEEP#_17") (pintype "unspecified"))
    )
    (net (code "31") (name "/NRST") (class "Default")
      (node (ref "C7") (pin "2") (pinfunction "2_2") (pintype "unspecified"))
      (node (ref "R1") (pin "1") (pinfunction "1_1") (pintype "unspecified"))
      (node (ref "SW1") (pin "2") (pinfunction "2_2") (pintype "unspecified"))
      (node (ref "U1") (pin "7") (pinfunction "NRST_7") (pintype "unspecified"))
    )
    (net (code "32") (name "/OSC_IN") (class "Default")
      (node (ref "C1") (pin "1") (pinfunction "1_1") (pintype "unspecified"))
      (node (ref "U1") (pin "5") (pinfunction "PD0-OSC_IN_5") (pintype "unspecified"))
      (node (ref "X1") (pin "1") (pinfunction "OSC1_1") (pintype "unspecified"))
    )
    (net (code "33") (name "/OSC_OUT") (class "Default")
      (node (ref "C8") (pin "1") (pinfunction "1_1") (pintype "unspecified"))
      (node (ref "U1") (pin "6") (pinfunction "PD1-OSC_OUT_6") (pintype "unspecified"))
      (node (ref "X1") (pin "3") (pinfunction "OSC2_3") (pintype "unspecified"))
    )
    (net (code "34") (name "/SWCLK") (class "Default")
      (node (ref "U1") (pin "37") (pinfunction "PA14JTCKSWCLK_37") (pintype "unspecified"))
      (node (ref "U2") (pin "2") (pinfunction "2_2") (pintype "unspecified"))
    )
    (net (code "35") (name "/SWDIO") (class "Default")
      (node (ref "U1") (pin "34") (pinfunction "PA13JTMSSWDIO_34") (pintype "unspecified"))
      (node (ref "U2") (pin "3") (pinfunction "3_3") (pintype "unspecified"))
    )
    (net (code "36") (name "/TIM1_CH1") (class "Default")
      (node (ref "U1") (pin "29") (pinfunction "PA8USART1_CKTIM1_CH1MCO_29") (pintype "unspecified"))
      (node (ref "U4") (pin "27") (pinfunction "IN1_27") (pintype "unspecified"))
    )
    (net (code "37") (name "/TIM1_CH2") (class "Default")
      (node (ref "U1") (pin "30") (pinfunction "PA9USART1_TXTIM1_CH2_30") (pintype "unspecified"))
      (node (ref "U4") (pin "25") (pinfunction "IN2_25") (pintype "unspecified"))
    )
    (net (code "38") (name "/TIM1_CH3") (class "Default")
      (node (ref "U1") (pin "31") (pinfunction "PA10USART1_RXTIM1_CH3_31") (pintype "unspecified"))
      (node (ref "U4") (pin "23") (pinfunction "IN3_23") (pintype "unspecified"))
    )
    (net (code "39") (name "/TIM2_CH1") (class "Default")
      (node (ref "R16") (pin "1") (pinfunction "1_1") (pintype "input"))
      (node (ref "U1") (pin "38") (pinfunction "PA15JTDI_38") (pintype "unspecified"))
    )
    (net (code "40") (name "/TIM2_CH2") (class "Default")
      (node (ref "R17") (pin "1") (pinfunction "1_1") (pintype "input"))
      (node (ref "U1") (pin "39") (pinfunction "PB3JTDO_39") (pintype "unspecified"))
    )
    (net (code "41") (name "/TIM3_CH1") (class "Default")
      (node (ref "U1") (pin "16") (pinfunction "PA6SPI1_MISOADC12_IN6TIM3_CH1_16") (pintype "unspecified"))
      (node (ref "U5") (pin "27") (pinfunction "IN1_27") (pintype "unspecified"))
    )
    (net (code "42") (name "/TIM3_CH2") (class "Default")
      (node (ref "U1") (pin "17") (pinfunction "PA7SPI1_MOSIADC12_IN7TIM3_CH2_17") (pintype "unspecified"))
      (node (ref "U5") (pin "25") (pinfunction "IN2_25") (pintype "unspecified"))
    )
    (net (code "43") (name "/TIM3_CH3") (class "Default")
      (node (ref "U1") (pin "18") (pinfunction "PB0ADC12_IN8TIM3_CH3_18") (pintype "unspecified"))
      (node (ref "U5") (pin "23") (pinfunction "IN3_23") (pintype "unspecified"))
    )
    (net (code "44") (name "/USART1_RX") (class "Default")
      (node (ref "U1") (pin "43") (pinfunction "PB7I2C1_SDATIM4_CH2_43") (pintype "unspecified"))
      (node (ref "U14") (pin "1") (pinfunction "1_1") (pintype "unspecified"))
    )
    (net (code "45") (name "/USART1_TX") (class "Default")
      (node (ref "U1") (pin "42") (pinfunction "PB6I2C1_SCLTIM4_CH1_42") (pintype "unspecified"))
      (node (ref "U14") (pin "2") (pinfunction "2_2") (pintype "unspecified"))
    )
    (net (code "46") (name "GND") (class "Default")
      (node (ref "C1") (pin "2") (pinfunction "2_2") (pintype "unspecified"))
      (node (ref "C15") (pin "1") (pinfunction "1_1") (pintype "unspecified"))
      (node (ref "C16") (pin "2") (pinfunction "2_2") (pintype "unspecified"))
      (node (ref "C17") (pin "2") (pinfunction "2_2") (pintype "unspecified"))
      (node (ref "C18") (pin "1") (pinfunction "1_1") (pintype "unspecified"))
      (node (ref "C19") (pin "2") (pinfunction "2_2") (pintype "unspecified"))
      (node (ref "C2") (pin "1") (pinfunction "1_1") (pintype "unspecified"))
      (node (ref "C22") (pin "1") (pinfunction "1_1") (pintype "input"))
      (node (ref "C23") (pin "1") (pinfunction "1_1") (pintype "input"))
      (node (ref "C3") (pin "1") (pinfunction "1_1") (pintype "unspecified"))
      (node (ref "C4") (pin "1") (pinfunction "1_1") (pintype "unspecified"))
      (node (ref "C5") (pin "1") (pinfunction "1_1") (pintype "unspecified"))
      (node (ref "C6") (pin "1") (pinfunction "1_1") (pintype "unspecified"))
      (node (ref "C7") (pin "1") (pinfunction "1_1") (pintype "unspecified"))
      (node (ref "C8") (pin "2") (pinfunction "2_2") (pintype "unspecified"))
      (node (ref "D1") (pin "2") (pinfunction "A_2") (pintype "unspecified"))
      (node (ref "D2") (pin "2") (pinfunction "2_2") (pintype "input"))
      (node (ref "Q1") (pin "2") (pinfunction "E_2") (pintype "unspecified"))
      (node (ref "Q2") (pin "2") (pinfunction "E_2") (pintype "unspecified"))
      (node (ref "R9") (pin "2") (pinfunction "2_2") (pintype "input"))
      (node (ref "SW1") (pin "1") (pinfunction "1_1") (pintype "unspecified"))
      (node (ref "U1") (pin "20") (pinfunction "PB2BOOT1_20") (pintype "unspecified"))
      (node (ref "U1") (pin "23") (pinfunction "VSS_1_23") (pintype "unspecified"))
      (node (ref "U1") (pin "35") (pinfunction "VSS_2_35") (pintype "unspecified"))
      (node (ref "U1") (pin "44") (pinfunction "BOOT0_44") (pintype "unspecified"))
      (node (ref "U1") (pin "47") (pinfunction "VSS_3_47") (pintype "unspecified"))
      (node (ref "U1") (pin "8") (pinfunction "VSS_A_8") (pintype "unspecified"))
      (node (ref "U10") (pin "1") (pinfunction "NC_1") (pintype "input"))
      (node (ref "U10") (pin "4") (pinfunction "GND_4") (pintype "input"))
      (node (ref "U10") (pin "7") (pinfunction "REF1_7") (pintype "input"))
      (node (ref "U11") (pin "1") (pinfunction "NC_1") (pintype "input"))
      (node (ref "U11") (pin "4") (pinfunction "GND_4") (pintype "input"))
      (node (ref "U11") (pin "7") (pinfunction "REF1_7") (pintype "input"))
      (node (ref "U12") (pin "2") (pinfunction "2_2") (pintype "unspecified"))
      (node (ref "U12") (pin "5") (pinfunction "5_5") (pintype "unspecified"))
      (node (ref "U12") (pin "6") (pinfunction "6_6") (pintype "unspecified"))
      (node (ref "U13") (pin "2") (pinfunction "2_2") (pintype "unspecified"))
      (node (ref "U13") (pin "5") (pinfunction "5_5") (pintype "unspecified"))
      (node (ref "U13") (pin "6") (pinfunction "6_6") (pintype "unspecified"))
      (node (ref "U14") (pin "3") (pinfunction "3_3") (pintype "unspecified"))
      (node (ref "U14") (pin "5") (pinfunction "5_5") (pintype "unspecified"))
      (node (ref "U14") (pin "6") (pinfunction "6_6") (pintype "unspecified"))
      (node (ref "U15") (pin "1") (pinfunction "NC_1") (pintype "input"))
      (node (ref "U15") (pin "4") (pinfunction "GND_4") (pintype "input"))
      (node (ref "U15") (pin "7") (pinfunction "REF1_7") (pintype "input"))
      (node (ref "U16") (pin "1") (pinfunction "NC_1") (pintype "input"))
      (node (ref "U16") (pin "4") (pinfunction "GND_4") (pintype "input"))
      (node (ref "U16") (pin "7") (pinfunction "REF1_7") (pintype "input"))
      (node (ref "U2") (pin "1") (pinfunction "1_1") (pintype "unspecified"))
      (node (ref "U2") (pin "5") (pinfunction "5_5") (pintype "unspecified"))
      (node (ref "U2") (pin "6") (pinfunction "6_6") (pintype "unspecified"))
      (node (ref "U3") (pin "3") (pinfunction "OUT-_3") (pintype "unspecified"))
      (node (ref "U4") (pin "12") (pinfunction "COMPP_12") (pintype "unspecified"))
      (node (ref "U4") (pin "13") (pinfunction "COMPN_13") (pintype "unspecified"))
      (node (ref "U4") (pin "14") (pinfunction "GND_14") (pintype "unspecified"))
      (node (ref "U4") (pin "19") (pinfunction "COMPO#_19") (pintype "unspecified"))
      (node (ref "U4") (pin "20") (pinfunction "GND_20") (pintype "unspecified"))
      (node (ref "U4") (pin "28") (pinfunction "GND_28") (pintype "unspecified"))
      (node (ref "U5") (pin "12") (pinfunction "COMPP_12") (pintype "unspecified"))
      (node (ref "U5") (pin "13") (pinfunction "COMPN_13") (pintype "unspecified"))
      (node (ref "U5") (pin "14") (pinfunction "GND_14") (pintype "unspecified"))
      (node (ref "U5") (pin "19") (pinfunction "COMPO#_19") (pintype "unspecified"))
      (node (ref "U5") (pin "20") (pinfunction "GND_20") (pintype "unspecified"))
      (node (ref "U5") (pin "28") (pinfunction "GND_28") (pintype "unspecified"))
      (node (ref "U6") (pin "1") (pinfunction "GND_1") (pintype "unspecified"))
      (node (ref "U7") (pin "2") (pinfunction "GND_2") (pintype "unspecified"))
      (node (ref "U7") (pin "8") (pinfunction "S_8") (pintype "unspecified"))
      (node (ref "U8") (pin "2") (pinfunction "2_2") (pintype "unspecified"))
      (node (ref "U8") (pin "5") (pinfunction "5_5") (pintype "unspecified"))
      (node (ref "U8") (pin "6") (pinfunction "6_6") (pintype "unspecified"))
      (node (ref "U9") (pin "2") (pinfunction "2_2") (pintype "unspecified"))
      (node (ref "U9") (pin "5") (pinfunction "5_5") (pintype "unspecified"))
      (node (ref "U9") (pin "6") (pinfunction "6_6") (pintype "unspecified"))
      (node (ref "X1") (pin "2") (pinfunction "GND_2") (pintype "unspecified"))
      (node (ref "X1") (pin "4") (pinfunction "GND_4") (pintype "unspecified"))
    )
    (net (code "47") (name "Net-(D3-Pad1)") (class "Default")
      (node (ref "D3") (pin "1") (pinfunction "1_1") (pintype "unspecified"))
      (node (ref "R9") (pin "1") (pinfunction "1_1") (pintype "input"))
    )
    (net (code "48") (name "Net-(D4-Pad1)") (class "Default")
      (node (ref "D4") (pin "1") (pinfunction "1_1") (pintype "unspecified"))
      (node (ref "R14") (pin "1") (pinfunction "1_1") (pintype "input"))
    )
    (net (code "49") (name "Net-(D5-Pad1)") (class "Default")
      (node (ref "D5") (pin "1") (pinfunction "1_1") (pintype "unspecified"))
      (node (ref "R15") (pin "1") (pinfunction "1_1") (pintype "input"))
    )
    (net (code "50") (name "Net-(Q1-B)") (class "Default")
      (node (ref "Q1") (pin "1") (pinfunction "B_1") (pintype "unspecified"))
      (node (ref "R16") (pin "2") (pinfunction "2_2") (pintype "input"))
    )
    (net (code "51") (name "Net-(Q1-C)") (class "Default")
      (node (ref "Q1") (pin "3") (pinfunction "C_3") (pintype "unspecified"))
      (node (ref "R14") (pin "2") (pinfunction "2_2") (pintype "input"))
    )
    (net (code "52") (name "Net-(Q2-B)") (class "Default")
      (node (ref "Q2") (pin "1") (pinfunction "B_1") (pintype "unspecified"))
      (node (ref "R17") (pin "2") (pinfunction "2_2") (pintype "input"))
    )
    (net (code "53") (name "Net-(Q2-C)") (class "Default")
      (node (ref "Q2") (pin "3") (pinfunction "C_3") (pintype "unspecified"))
      (node (ref "R15") (pin "2") (pinfunction "2_2") (pintype "input"))
    )
    (net (code "54") (name "Net-(SW2-A1)") (class "Default")
      (node (ref "R2") (pin "1") (pinfunction "1_1") (pintype "input"))
      (node (ref "SW2") (pin "1") (pinfunction "A1_1") (pintype "input"))
    )
    (net (code "55") (name "Net-(U4-CP1)") (class "Default")
      (node (ref "C9") (pin "2") (pinfunction "2_2") (pintype "input"))
      (node (ref "U4") (pin "1") (pinfunction "CP1_1") (pintype "unspecified"))
    )
    (net (code "56") (name "Net-(U4-CP2)") (class "Default")
      (node (ref "C9") (pin "1") (pinfunction "1_1") (pintype "input"))
      (node (ref "U4") (pin "2") (pinfunction "CP2_2") (pintype "unspecified"))
    )
    (net (code "57") (name "Net-(U4-V3P3OUT)") (class "Default")
      (node (ref "C22") (pin "2") (pinfunction "2_2") (pintype "input"))
      (node (ref "R3") (pin "1") (pinfunction "1_1") (pintype "input"))
      (node (ref "U4") (pin "15") (pinfunction "V3P3OUT_15") (pintype "unspecified"))
    )
    (net (code "58") (name "Net-(U4-VCP)") (class "Default")
      (node (ref "C11") (pin "2") (pinfunction "2_2") (pintype "input"))
      (node (ref "U4") (pin "3") (pinfunction "VCP_3") (pintype "unspecified"))
    )
    (net (code "59") (name "Net-(U5-CP1)") (class "Default")
      (node (ref "C10") (pin "2") (pinfunction "2_2") (pintype "input"))
      (node (ref "U5") (pin "1") (pinfunction "CP1_1") (pintype "unspecified"))
    )
    (net (code "60") (name "Net-(U5-CP2)") (class "Default")
      (node (ref "C10") (pin "1") (pinfunction "1_1") (pintype "input"))
      (node (ref "U5") (pin "2") (pinfunction "CP2_2") (pintype "unspecified"))
    )
    (net (code "61") (name "Net-(U5-V3P3OUT)") (class "Default")
      (node (ref "C23") (pin "2") (pinfunction "2_2") (pintype "input"))
      (node (ref "R4") (pin "1") (pinfunction "1_1") (pintype "input"))
      (node (ref "U5") (pin "15") (pinfunction "V3P3OUT_15") (pintype "unspecified"))
    )
    (net (code "62") (name "Net-(U5-VCP)") (class "Default")
      (node (ref "C12") (pin "2") (pinfunction "2_2") (pintype "input"))
      (node (ref "U5") (pin "3") (pinfunction "VCP_3") (pintype "unspecified"))
    )
    (net (code "63") (name "PGND") (class "Default")
      (node (ref "C13") (pin "1") (pinfunction "1_1") (pintype "input"))
      (node (ref "C14") (pin "1") (pinfunction "1_1") (pintype "input"))
      (node (ref "C20") (pin "2") (pinfunction "2_2") (pintype "input"))
      (node (ref "C21") (pin "2") (pinfunction "2_2") (pintype "input"))
      (node (ref "CN1") (pin "2") (pinfunction "2_2") (pintype "unspecified"))
      (node (ref "CN1") (pin "3") (pinfunction "3_3") (pintype "unspecified"))
      (node (ref "CN1") (pin "4") (pinfunction "4_4") (pintype "unspecified"))
      (node (ref "CN2") (pin "2") (pinfunction "2_2") (pintype "unspecified"))
      (node (ref "CN2") (pin "3") (pinfunction "3_3") (pintype "unspecified"))
      (node (ref "CN2") (pin "4") (pinfunction "4_4") (pintype "unspecified"))
      (node (ref "CN3") (pin "1") (pinfunction "-_1") (pintype "unspecified"))
      (node (ref "CN3") (pin "3") (pinfunction "3_3") (pintype "unspecified"))
      (node (ref "CN3") (pin "4") (pinfunction "4_4") (pintype "unspecified"))
      (node (ref "U3") (pin "1") (pinfunction "IN-_1") (pintype "unspecified"))
      (node (ref "U4") (pin "10") (pinfunction "PGND3_10") (pintype "unspecified"))
      (node (ref "U4") (pin "29") (pinfunction "EP_29") (pintype "unspecified"))
      (node (ref "U4") (pin "6") (pinfunction "PGND1_6") (pintype "unspecified"))
      (node (ref "U4") (pin "7") (pinfunction "PGND2_7") (pintype "unspecified"))
      (node (ref "U5") (pin "10") (pinfunction "PGND3_10") (pintype "unspecified"))
      (node (ref "U5") (pin "29") (pinfunction "EP_29") (pintype "unspecified"))
      (node (ref "U5") (pin "6") (pinfunction "PGND1_6") (pintype "unspecified"))
      (node (ref "U5") (pin "7") (pinfunction "PGND2_7") (pintype "unspecified"))
    )
    (net (code "64") (name "VCC") (class "Default")
      (node (ref "C15") (pin "2") (pinfunction "2_2") (pintype "unspecified"))
      (node (ref "C16") (pin "1") (pinfunction "1_1") (pintype "unspecified"))
      (node (ref "C19") (pin "1") (pinfunction "1_1") (pintype "unspecified"))
      (node (ref "D1") (pin "1") (pinfunction "C_1") (pintype "unspecified"))
      (node (ref "D3") (pin "2") (pinfunction "2_2") (pintype "unspecified"))
      (node (ref "D4") (pin "2") (pinfunction "2_2") (pintype "unspecified"))
      (node (ref "D5") (pin "2") (pinfunction "2_2") (pintype "unspecified"))
      (node (ref "U12") (pin "1") (pinfunction "1_1") (pintype "unspecified"))
      (node (ref "U13") (pin "1") (pinfunction "1_1") (pintype "unspecified"))
      (node (ref "U14") (pin "4") (pinfunction "4_4") (pintype "unspecified"))
      (node (ref "U3") (pin "4") (pinfunction "OUT+_4") (pintype "unspecified"))
      (node (ref "U6") (pin "3") (pinfunction "VIN_3") (pintype "unspecified"))
      (node (ref "U7") (pin "3") (pinfunction "VCC_3") (pintype "unspecified"))
      (node (ref "U8") (pin "1") (pinfunction "1_1") (pintype "unspecified"))
      (node (ref "U9") (pin "1") (pinfunction "1_1") (pintype "unspecified"))
    )
    (net (code "65") (name "VCC3.3") (class "Default")
      (node (ref "C17") (pin "1") (pinfunction "1_1") (pintype "unspecified"))
      (node (ref "C18") (pin "2") (pinfunction "2_2") (pintype "unspecified"))
      (node (ref "C2") (pin "2") (pinfunction "2_2") (pintype "unspecified"))
      (node (ref "C3") (pin "2") (pinfunction "2_2") (pintype "unspecified"))
      (node (ref "C4") (pin "2") (pinfunction "2_2") (pintype "unspecified"))
      (node (ref "C5") (pin "2") (pinfunction "2_2") (pintype "unspecified"))
      (node (ref "C6") (pin "2") (pinfunction "2_2") (pintype "unspecified"))
      (node (ref "D2") (pin "1") (pinfunction "1_1") (pintype "input"))
      (node (ref "R1") (pin "2") (pinfunction "2_2") (pintype "unspecified"))
      (node (ref "U1") (pin "1") (pinfunction "VBAT_1") (pintype "unspecified"))
      (node (ref "U1") (pin "24") (pinfunction "VDD_1_24") (pintype "unspecified"))
      (node (ref "U1") (pin "36") (pinfunction "VDD_2_36") (pintype "unspecified"))
      (node (ref "U1") (pin "48") (pinfunction "VDD_3_48") (pintype "unspecified"))
      (node (ref "U1") (pin "9") (pinfunction "VDD_A_9") (pintype "unspecified"))
      (node (ref "U10") (pin "5") (pinfunction "VS_5") (pintype "input"))
      (node (ref "U10") (pin "6") (pinfunction "REF2_6") (pintype "input"))
      (node (ref "U11") (pin "5") (pinfunction "VS_5") (pintype "input"))
      (node (ref "U11") (pin "6") (pinfunction "REF2_6") (pintype "input"))
      (node (ref "U15") (pin "5") (pinfunction "VS_5") (pintype "input"))
      (node (ref "U15") (pin "6") (pinfunction "REF2_6") (pintype "input"))
      (node (ref "U16") (pin "5") (pinfunction "VS_5") (pintype "input"))
      (node (ref "U16") (pin "6") (pinfunction "REF2_6") (pintype "input"))
      (node (ref "U2") (pin "4") (pinfunction "4_4") (pintype "unspecified"))
      (node (ref "U6") (pin "2") (pinfunction "VOUT_2") (pintype "unspecified"))
      (node (ref "U6") (pin "4") (pinfunction "VOUT_4") (pintype "unspecified"))
    )
    (net (code "66") (name "VCC12V") (class "Default")
      (node (ref "C11") (pin "1") (pinfunction "1_1") (pintype "input"))
      (node (ref "C12") (pin "1") (pinfunction "1_1") (pintype "input"))
      (node (ref "C13") (pin "2") (pinfunction "2_2") (pintype "input"))
      (node (ref "C14") (pin "2") (pinfunction "2_2") (pintype "input"))
      (node (ref "C20") (pin "1") (pinfunction "1_1") (pintype "input"))
      (node (ref "C21") (pin "1") (pinfunction "1_1") (pintype "input"))
      (node (ref "CN1") (pin "1") (pinfunction "1_1") (pintype "unspecified"))
      (node (ref "CN2") (pin "1") (pinfunction "1_1") (pintype "unspecified"))
      (node (ref "CN3") (pin "2") (pinfunction "+_2") (pintype "unspecified"))
      (node (ref "U3") (pin "2") (pinfunction "IN+_2") (pintype "unspecified"))
      (node (ref "U4") (pin "11") (pinfunction "VM_11") (pintype "unspecified"))
      (node (ref "U4") (pin "4") (pinfunction "VM_4") (pintype "unspecified"))
      (node (ref "U5") (pin "11") (pinfunction "VM_11") (pintype "unspecified"))
      (node (ref "U5") (pin "4") (pinfunction "VM_4") (pintype "unspecified"))
    )
    (net (code "67") (name "unconnected-(U1-PB1ADC12_IN9TIM3_CH4-Pad19)") (class "Default")
      (node (ref "U1") (pin "19") (pinfunction "PB1ADC12_IN9TIM3_CH4_19") (pintype "unspecified+no_connect"))
    )
    (net (code "68") (name "unconnected-(U1-PC13-TAMPER-RTC-Pad2)") (class "Default")
      (node (ref "U1") (pin "2") (pinfunction "PC13-TAMPER-RTC_2") (pintype "unspecified+no_connect"))
    )
    (net (code "69") (name "unconnected-(U1-PC14-OSC32_IN-Pad3)") (class "Default")
      (node (ref "U1") (pin "3") (pinfunction "PC14-OSC32_IN_3") (pintype "unspecified+no_connect"))
    )
    (net (code "70") (name "unconnected-(U1-PC15-OSC32_OUT-Pad4)") (class "Default")
      (node (ref "U1") (pin "4") (pinfunction "PC15-OSC32_OUT_4") (pintype "unspecified+no_connect"))
    )
    (net (code "71") (name "unconnected-(U4-NC-Pad21)") (class "Default")
      (node (ref "U4") (pin "21") (pinfunction "NC_21") (pintype "unspecified+no_connect"))
    )
    (net (code "72") (name "unconnected-(U5-NC-Pad21)") (class "Default")
      (node (ref "U5") (pin "21") (pinfunction "NC_21") (pintype "unspecified+no_connect"))
    )
    (net (code "73") (name "unconnected-(U7-VREF-Pad5)") (class "Default")
      (node (ref "U7") (pin "5") (pinfunction "VREF_5") (pintype "unspecified+no_connect"))
    )
  )
)
